# SparkFun_RTK_Facet_-_Main.net
KiCad netlist of a schematic drawn in EAGLE
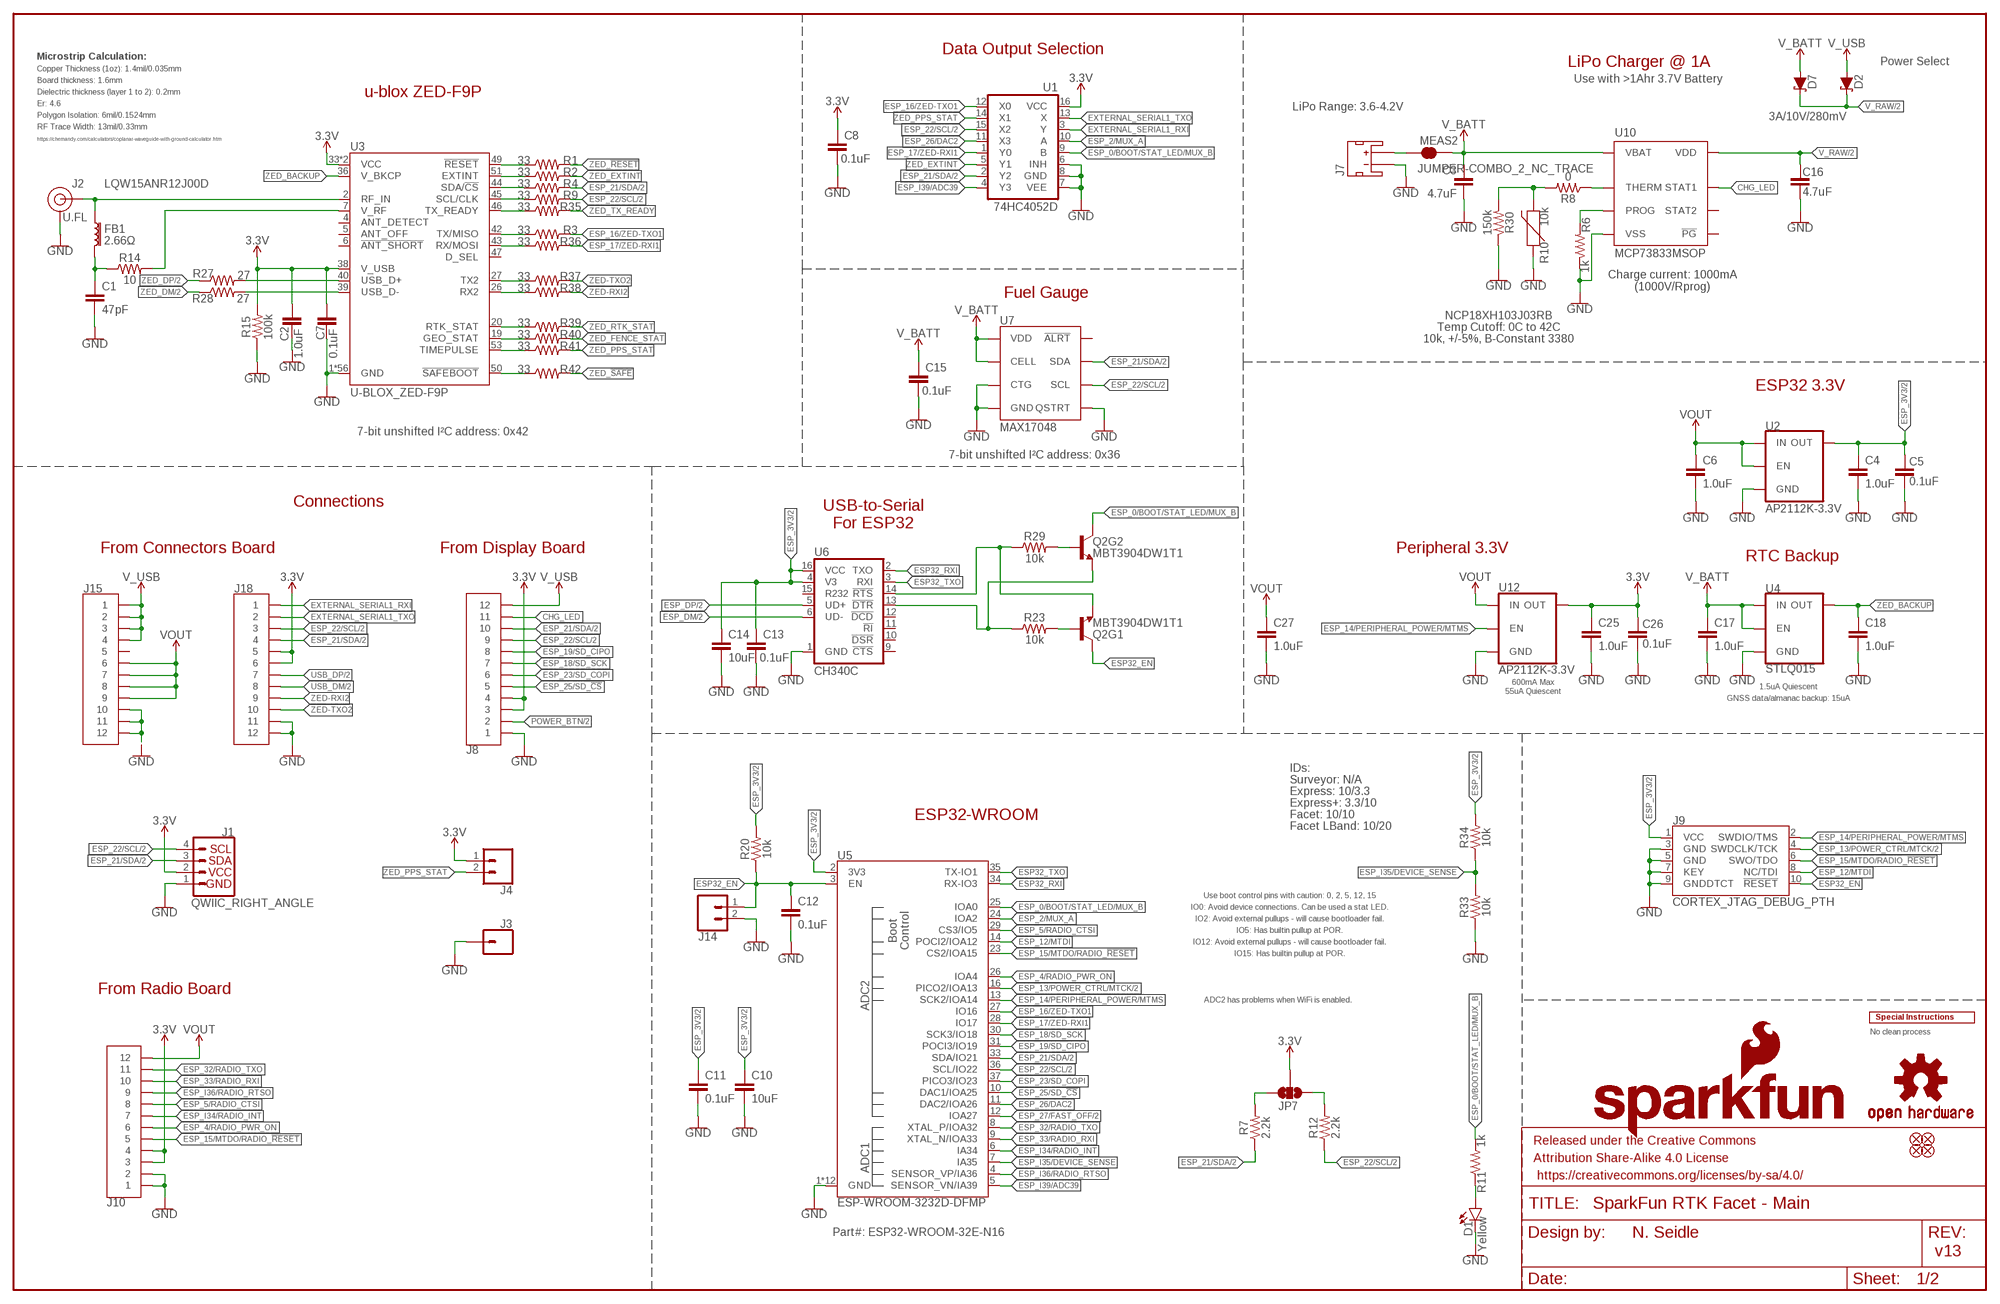
[diagram p0: schematic, sheet 1]
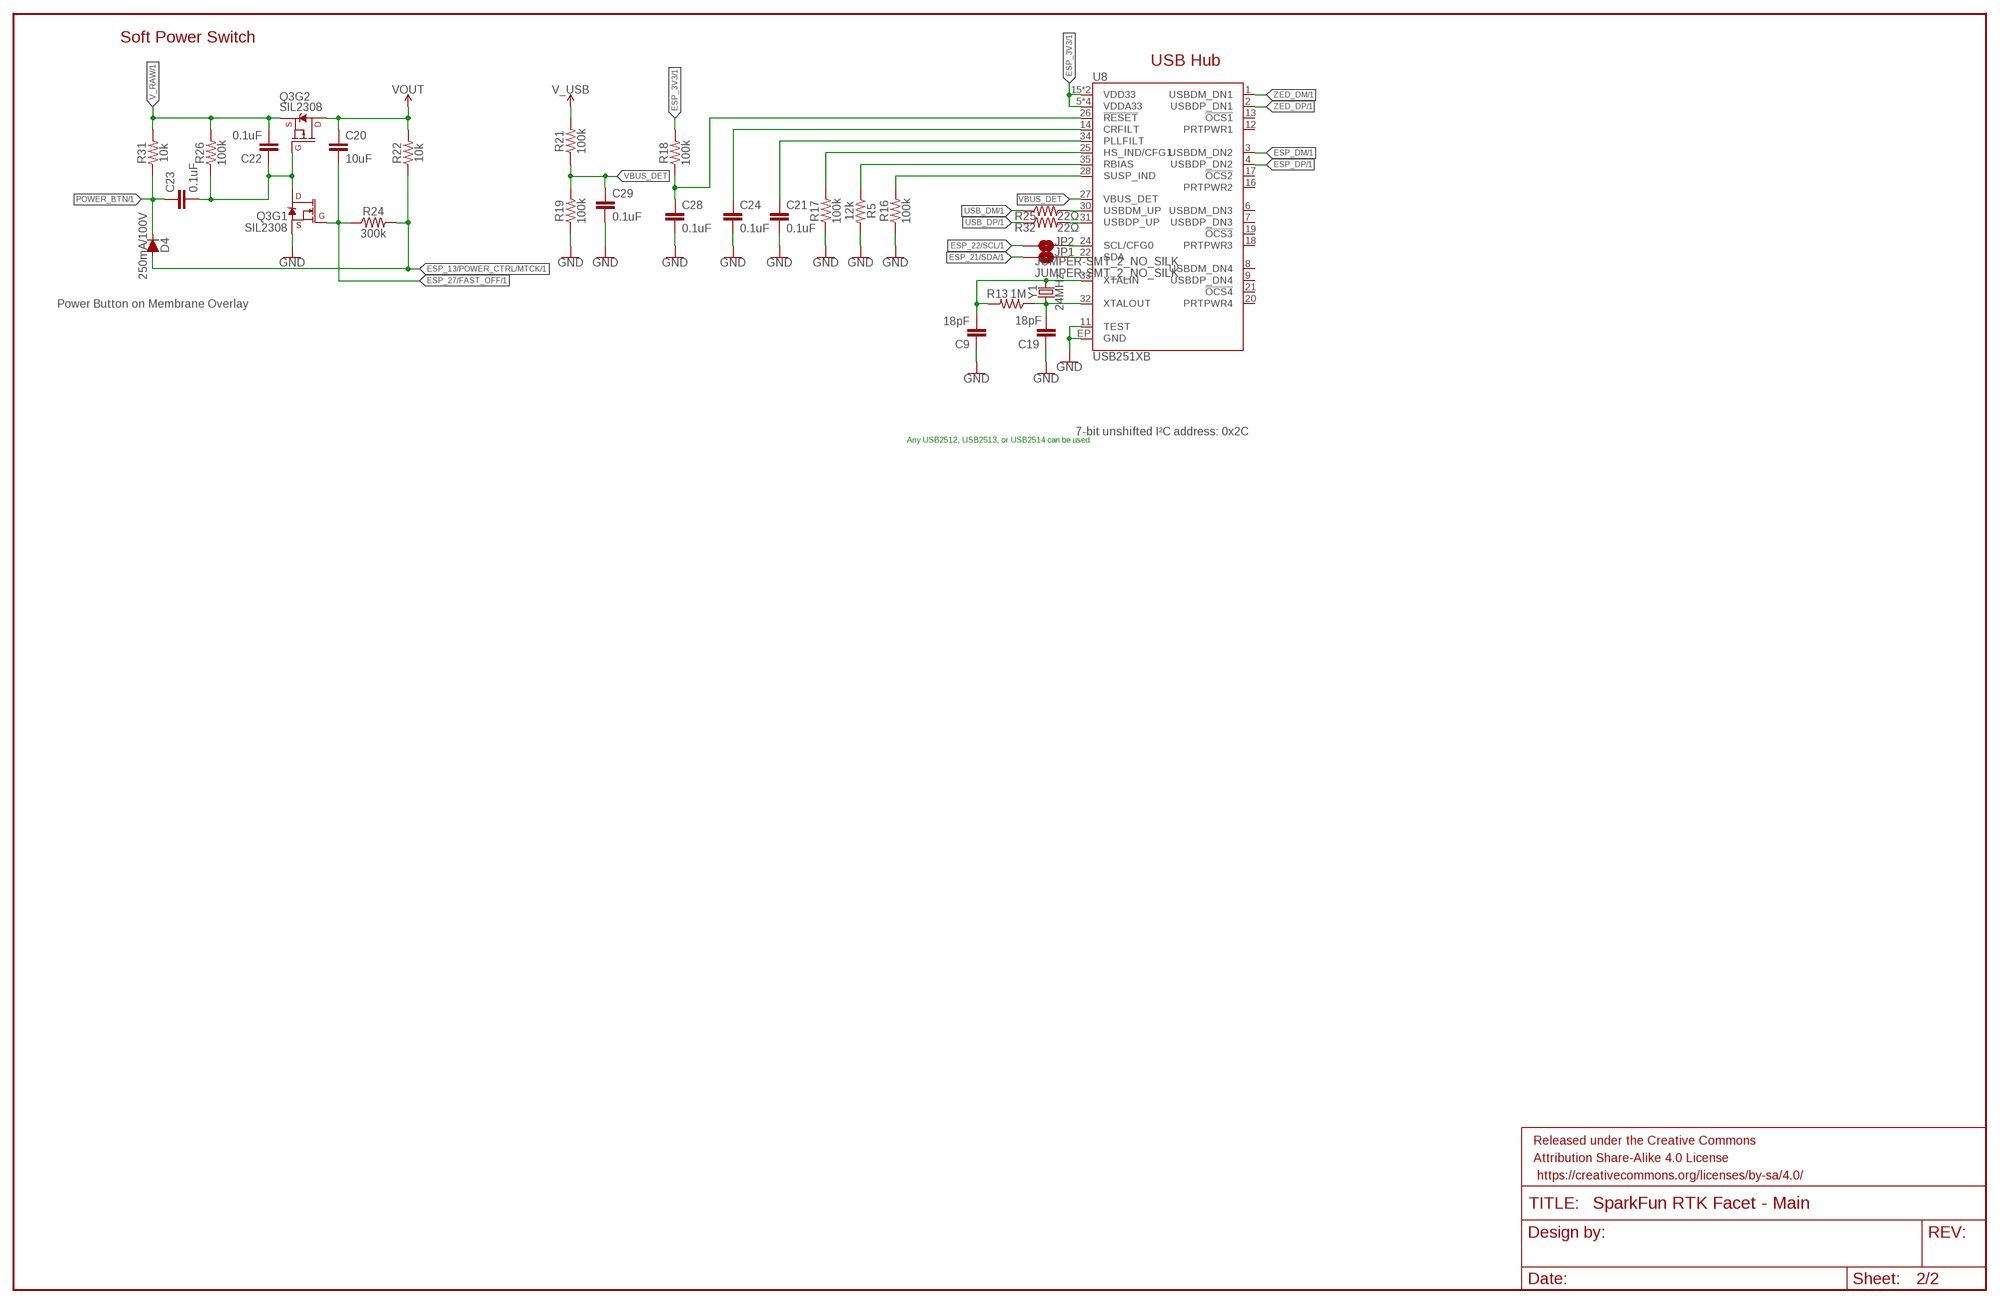
[diagram p1: schematic, sheet 2]

(export (version "E")
  (design (tool "Eeschema 10.0.6"))
  (components
    (comp (ref "C1")
      (value "47pF")
      (footprint "eagle-import:0402")
      (libsource (lib "eagle-import") (part "47PF-0402-25V-5%-X7R"))
    )
    (comp (ref "C2")
      (value "1.0uF")
      (footprint "eagle-import:0603")
      (libsource (lib "eagle-import") (part "1.0UF-0603-16V-10%-X7R"))
    )
    (comp (ref "C3")
      (value "4.7uF")
      (footprint "eagle-import:0603")
      (libsource (lib "eagle-import") (part "4.7UF-0603-35V-(20%)"))
    )
    (comp (ref "C4")
      (value "1.0uF")
      (footprint "eagle-import:0603")
      (libsource (lib "eagle-import") (part "1.0UF-0603-16V-10%-X7R"))
    )
    (comp (ref "C5")
      (value "0.1uF")
      (footprint "eagle-import:0603")
      (libsource (lib "eagle-import") (part "0.1UF-0603-25V-5%"))
    )
    (comp (ref "C6")
      (value "1.0uF")
      (footprint "eagle-import:0603")
      (libsource (lib "eagle-import") (part "1.0UF-0603-16V-10%-X7R"))
    )
    (comp (ref "C7")
      (value "0.1uF")
      (footprint "eagle-import:0603")
      (libsource (lib "eagle-import") (part "0.1UF-0603-25V-5%"))
    )
    (comp (ref "C8")
      (value "0.1uF")
      (footprint "eagle-import:0603")
      (libsource (lib "eagle-import") (part "0.1UF-0603-25V-(+80/-20%)"))
    )
    (comp (ref "C10")
      (value "10uF")
      (footprint "eagle-import:0603")
      (libsource (lib "eagle-import") (part "10UF-0603-6.3V-20%"))
    )
    (comp (ref "C11")
      (value "0.1uF")
      (footprint "eagle-import:0603")
      (libsource (lib "eagle-import") (part "0.1UF-0603-25V-(+80/-20%)"))
    )
    (comp (ref "C12")
      (value "0.1uF")
      (footprint "eagle-import:0603")
      (libsource (lib "eagle-import") (part "0.1UF-0603-25V-(+80/-20%)"))
    )
    (comp (ref "C13")
      (value "0.1uF")
      (footprint "eagle-import:0603")
      (libsource (lib "eagle-import") (part "0.1UF-0603-25V-(+80/-20%)"))
    )
    (comp (ref "C14")
      (value "10uF")
      (footprint "eagle-import:0603")
      (libsource (lib "eagle-import") (part "10UF-0603-6.3V-20%"))
    )
    (comp (ref "C15")
      (value "0.1uF")
      (footprint "eagle-import:0603")
      (libsource (lib "eagle-import") (part "0.1UF-0603-25V-(+80/-20%)"))
    )
    (comp (ref "C16")
      (value "4.7uF")
      (footprint "eagle-import:0603")
      (libsource (lib "eagle-import") (part "4.7UF-0603-35V-(20%)"))
    )
    (comp (ref "C17")
      (value "1.0uF")
      (footprint "eagle-import:0603")
      (libsource (lib "eagle-import") (part "1.0UF-0603-16V-10%-X7R"))
    )
    (comp (ref "C18")
      (value "1.0uF")
      (footprint "eagle-import:0603")
      (libsource (lib "eagle-import") (part "1.0UF-0603-16V-10%-X7R"))
    )
    (comp (ref "C25")
      (value "1.0uF")
      (footprint "eagle-import:0603")
      (libsource (lib "eagle-import") (part "1.0UF-0603-16V-10%-X7R"))
    )
    (comp (ref "C26")
      (value "0.1uF")
      (footprint "eagle-import:0603")
      (libsource (lib "eagle-import") (part "0.1UF-0603-25V-5%"))
    )
    (comp (ref "C27")
      (value "1.0uF")
      (footprint "eagle-import:0603")
      (libsource (lib "eagle-import") (part "1.0UF-0603-16V-10%-X7R"))
    )
    (comp (ref "D1")
      (value "Yellow")
      (footprint "eagle-import:LED-0603")
      (libsource (lib "eagle-import") (part "LED-YELLOW0603"))
    )
    (comp (ref "D2")
      (value "3A/10V/280mV")
      (footprint "eagle-import:SOD-323")
      (libsource (lib "eagle-import") (part "DIODE-SCHOTTKY-BAT60A"))
    )
    (comp (ref "D7")
      (value "3A/10V/280mV")
      (footprint "eagle-import:SOD-323")
      (libsource (lib "eagle-import") (part "DIODE-SCHOTTKY-BAT60A"))
    )
    (comp (ref "FB1")
      (value "2.66Ω")
      (footprint "eagle-import:0402-TIGHT")
      (libsource (lib "eagle-import") (part "FERRITE_BEAD-0402-2.66Ω-1GHZ"))
    )
    (comp (ref "FRAME2")
      (value "FRAME-LEDGER")
      (footprint "eagle-import:CREATIVE_COMMONS")
      (libsource (lib "eagle-import") (part "FRAME-LEDGER"))
    )
    (comp (ref "J1")
      (value "QWIIC_RIGHT_ANGLE")
      (footprint "eagle-import:JST04_1MM_RA")
      (libsource (lib "eagle-import") (part "QWIIC_CONNECTORJS-1MM"))
    )
    (comp (ref "J2")
      (value "U.FL")
      (footprint "eagle-import:U.FL")
      (libsource (lib "eagle-import") (part "U.FL2PIN"))
    )
    (comp (ref "J3")
      (value "CONN_01PTH_NO_SILK_YES_STOP")
      (footprint "eagle-import:1X01_NO_SILK")
      (libsource (lib "eagle-import") (part "CONN_01PTH_NO_SILK_YES_STOP"))
    )
    (comp (ref "J4")
      (value "CONN_021X02_NO_SILK")
      (footprint "eagle-import:1X02_NO_SILK")
      (libsource (lib "eagle-import") (part "CONN_021X02_NO_SILK"))
    )
    (comp (ref "J7")
      (value "JST_2MM_MALE")
      (footprint "eagle-import:JST-2-SMD")
      (libsource (lib "eagle-import") (part "JST_2MM_MALE"))
    )
    (comp (ref "J8")
      (value "FPC_12_0.5MM_BACKFLIP")
      (footprint "eagle-import:FPC_12_DOUBLESIDED_BACKFLIP")
      (libsource (lib "eagle-import") (part "FPC_12_0.5MM_BACKFLIP"))
    )
    (comp (ref "J9")
      (value "CORTEX_JTAG_DEBUG_PTH")
      (footprint "eagle-import:2X5-PTH-1.27MM")
      (libsource (lib "eagle-import") (part "CORTEX_JTAG_DEBUG_PTH"))
    )
    (comp (ref "J10")
      (value "FPC_12_0.5MM_BACKFLIP")
      (footprint "eagle-import:FPC_12_DOUBLESIDED_BACKFLIP")
      (libsource (lib "eagle-import") (part "FPC_12_0.5MM_BACKFLIP"))
    )
    (comp (ref "J14")
      (value "CONN_021X02_NO_SILK")
      (footprint "eagle-import:1X02_NO_SILK")
      (libsource (lib "eagle-import") (part "CONN_021X02_NO_SILK"))
    )
    (comp (ref "J15")
      (value "FPC_12_0.5MM_BACKFLIP")
      (footprint "eagle-import:FPC_12_DOUBLESIDED_BACKFLIP")
      (libsource (lib "eagle-import") (part "FPC_12_0.5MM_BACKFLIP"))
    )
    (comp (ref "J18")
      (value "FPC_12_0.5MM_BACKFLIP")
      (footprint "eagle-import:FPC_12_DOUBLESIDED_BACKFLIP")
      (libsource (lib "eagle-import") (part "FPC_12_0.5MM_BACKFLIP"))
    )
    (comp (ref "JP7")
      (value "JUMPER-SMT_3_NO_SILK")
      (footprint "eagle-import:SMT-JUMPER_3_NO_SILK")
      (libsource (lib "eagle-import") (part "JUMPER-SMT_3_NO_SILK"))
    )
    (comp (ref "JP21")
      (value "FIDUCIALUFIDUCIAL")
      (footprint "eagle-import:FIDUCIAL-MICRO")
      (libsource (lib "eagle-import") (part "FIDUCIALUFIDUCIAL"))
    )
    (comp (ref "JP61")
      (value "FIDUCIALUFIDUCIAL")
      (footprint "eagle-import:FIDUCIAL-MICRO")
      (libsource (lib "eagle-import") (part "FIDUCIALUFIDUCIAL"))
    )
    (comp (ref "JP71")
      (value "FIDUCIALUFIDUCIAL")
      (footprint "eagle-import:FIDUCIAL-MICRO")
      (libsource (lib "eagle-import") (part "FIDUCIALUFIDUCIAL"))
    )
    (comp (ref "JP81")
      (value "FIDUCIALUFIDUCIAL")
      (footprint "eagle-import:FIDUCIAL-MICRO")
      (libsource (lib "eagle-import") (part "FIDUCIALUFIDUCIAL"))
    )
    (comp (ref "LOGO1")
      (value "OSHW-LOGOMINI")
      (footprint "eagle-import:OSHW-LOGO-MINI")
      (libsource (lib "eagle-import") (part "OSHW-LOGOMINI"))
    )
    (comp (ref "LOGO2")
      (value "SFE_LOGO_NAME_FLAME.1_INCH")
      (footprint "eagle-import:SFE_LOGO_NAME_FLAME_.1")
      (libsource (lib "eagle-import") (part "SFE_LOGO_NAME_FLAME.1_INCH"))
    )
    (comp (ref "MEAS2")
      (value "JUMPER-COMBO_2_NC_TRACE")
      (footprint "eagle-import:COMBO-JUMPER_2_NC_TRACE")
      (libsource (lib "eagle-import") (part "JUMPER-COMBO_2_NC_TRACE"))
    )
    (comp (ref "Q2")
      (value "MBT3904DW1T1")
      (footprint "eagle-import:SC70-6")
      (libsource (lib "eagle-import") (part "TRANS_NPN_DUAL-MBT3904DW1T1"))
    )
    (comp (ref "R1")
      (value "33")
      (footprint "eagle-import:0603")
      (libsource (lib "eagle-import") (part "33OHM-0603-1/10W-1%"))
    )
    (comp (ref "R2")
      (value "33")
      (footprint "eagle-import:0603")
      (libsource (lib "eagle-import") (part "33OHM-0603-1/10W-1%"))
    )
    (comp (ref "R3")
      (value "33")
      (footprint "eagle-import:0603")
      (libsource (lib "eagle-import") (part "33OHM-0603-1/10W-1%"))
    )
    (comp (ref "R4")
      (value "33")
      (footprint "eagle-import:0603")
      (libsource (lib "eagle-import") (part "33OHM-0603-1/10W-1%"))
    )
    (comp (ref "R6")
      (value "1k")
      (footprint "eagle-import:0603")
      (libsource (lib "eagle-import") (part "1KOHM-0603-1/10W-1%"))
    )
    (comp (ref "R7")
      (value "2.2k")
      (footprint "eagle-import:0603")
      (libsource (lib "eagle-import") (part "2.2KOHM-0603-1/10W-1%"))
    )
    (comp (ref "R8")
      (value "0")
      (footprint "eagle-import:0603")
      (libsource (lib "eagle-import") (part "0OHM-0603-1/10W"))
    )
    (comp (ref "R9")
      (value "33")
      (footprint "eagle-import:0603")
      (libsource (lib "eagle-import") (part "33OHM-0603-1/10W-1%"))
    )
    (comp (ref "R10")
      (value "10k")
      (footprint "eagle-import:0603")
      (libsource (lib "eagle-import") (part "NTC-THERMISTOR-0603"))
    )
    (comp (ref "R11")
      (value "1k")
      (footprint "eagle-import:0603")
      (libsource (lib "eagle-import") (part "1KOHM-0603-1/10W-1%"))
    )
    (comp (ref "R12")
      (value "2.2k")
      (footprint "eagle-import:0603")
      (libsource (lib "eagle-import") (part "2.2KOHM-0603-1/10W-1%"))
    )
    (comp (ref "R14")
      (value "10")
      (footprint "eagle-import:0603")
      (libsource (lib "eagle-import") (part "10OHM-0603-1/10W-1%"))
    )
    (comp (ref "R15")
      (value "100k")
      (footprint "eagle-import:0603")
      (libsource (lib "eagle-import") (part "100KOHM-0603-1/10W-1%"))
    )
    (comp (ref "R20")
      (value "10k")
      (footprint "eagle-import:0603")
      (libsource (lib "eagle-import") (part "10KOHM-0603-1/10W-1%"))
    )
    (comp (ref "R23")
      (value "10k")
      (footprint "eagle-import:0603")
      (libsource (lib "eagle-import") (part "10KOHM-0603-1/10W-1%"))
    )
    (comp (ref "R27")
      (value "27")
      (footprint "eagle-import:0603")
      (libsource (lib "eagle-import") (part "27OHM-0603-1/10W-1%"))
    )
    (comp (ref "R28")
      (value "27")
      (footprint "eagle-import:0603")
      (libsource (lib "eagle-import") (part "27OHM-0603-1/10W-1%"))
    )
    (comp (ref "R29")
      (value "10k")
      (footprint "eagle-import:0603")
      (libsource (lib "eagle-import") (part "10KOHM-0603-1/10W-1%"))
    )
    (comp (ref "R30")
      (value "150k")
      (footprint "eagle-import:0603")
      (libsource (lib "eagle-import") (part "150KOHM-0603-1/10W-1%"))
    )
    (comp (ref "R33")
      (value "10k")
      (footprint "eagle-import:0603")
      (libsource (lib "eagle-import") (part "10KOHM-0603-1/10W-1%"))
    )
    (comp (ref "R34")
      (value "10k")
      (footprint "eagle-import:0603")
      (libsource (lib "eagle-import") (part "10KOHM-0603-1/10W-1%"))
    )
    (comp (ref "R35")
      (value "33")
      (footprint "eagle-import:0603")
      (libsource (lib "eagle-import") (part "33OHM-0603-1/10W-1%"))
    )
    (comp (ref "R36")
      (value "33")
      (footprint "eagle-import:0603")
      (libsource (lib "eagle-import") (part "33OHM-0603-1/10W-1%"))
    )
    (comp (ref "R37")
      (value "33")
      (footprint "eagle-import:0603")
      (libsource (lib "eagle-import") (part "33OHM-0603-1/10W-1%"))
    )
    (comp (ref "R38")
      (value "33")
      (footprint "eagle-import:0603")
      (libsource (lib "eagle-import") (part "33OHM-0603-1/10W-1%"))
    )
    (comp (ref "R39")
      (value "33")
      (footprint "eagle-import:0603")
      (libsource (lib "eagle-import") (part "33OHM-0603-1/10W-1%"))
    )
    (comp (ref "R40")
      (value "33")
      (footprint "eagle-import:0603")
      (libsource (lib "eagle-import") (part "33OHM-0603-1/10W-1%"))
    )
    (comp (ref "R41")
      (value "33")
      (footprint "eagle-import:0603")
      (libsource (lib "eagle-import") (part "33OHM-0603-1/10W-1%"))
    )
    (comp (ref "R42")
      (value "33")
      (footprint "eagle-import:0603")
      (libsource (lib "eagle-import") (part "33OHM-0603-1/10W-1%"))
    )
    (comp (ref "U$2")
      (value "SPECIAL_INSTRUCTIONS-ORDERING")
      (footprint "eagle-import:ORDERING_INSTRUCTIONS")
      (libsource (lib "eagle-import") (part "SPECIAL_INSTRUCTIONS-ORDERING"))
    )
    (comp (ref "U1")
      (value "74HC4052D")
      (footprint "eagle-import:SO16")
      (libsource (lib "eagle-import") (part "744052DHC"))
    )
    (comp (ref "U2")
      (value "AP2112K-3.3V")
      (footprint "eagle-import:SOT23-5")
      (libsource (lib "eagle-import") (part "V_REG_AP2112K-3.3V"))
    )
    (comp (ref "U3")
      (value "U-BLOX_ZED-F9P")
      (footprint "eagle-import:ZED-F9P")
      (libsource (lib "eagle-import") (part "U-BLOX_ZED-F9P"))
    )
    (comp (ref "U4")
      (value "STLQ015")
      (footprint "eagle-import:SOT23-5")
      (libsource (lib "eagle-import") (part "STLQ015-3.3V"))
    )
    (comp (ref "U5")
      (value "ESP-WROOM-3232D-DFMP")
      (footprint "eagle-import:ESP-WROOM-32D-DFM_PASTE")
      (libsource (lib "eagle-import") (part "ESP-WROOM-3232D-DFMP"))
    )
    (comp (ref "U6")
      (value "CH340C")
      (footprint "eagle-import:SO016")
      (libsource (lib "eagle-import") (part "CH340C"))
    )
    (comp (ref "U7")
      (value "MAX17048")
      (footprint "eagle-import:DFN-8")
      (libsource (lib "eagle-import") (part "MAX17048DFN8"))
    )
    (comp (ref "U10")
      (value "MCP73833MSOP")
      (footprint "eagle-import:MSOP10")
      (libsource (lib "eagle-import") (part "MCP73833MSOP"))
    )
    (comp (ref "U12")
      (value "AP2112K-3.3V")
      (footprint "eagle-import:SOT23-5")
      (libsource (lib "eagle-import") (part "V_REG_AP2112K-3.3V"))
    )
    (comp (ref "C9")
      (value "18pF")
      (footprint "eagle-import:0603")
      (libsource (lib "eagle-import") (part "18PF-0603-50V-5%"))
    )
    (comp (ref "C19")
      (value "18pF")
      (footprint "eagle-import:0603")
      (libsource (lib "eagle-import") (part "18PF-0603-50V-5%"))
    )
    (comp (ref "C20")
      (value "10uF")
      (footprint "eagle-import:0603")
      (libsource (lib "eagle-import") (part "10UF-0603-6.3V-20%"))
    )
    (comp (ref "C21")
      (value "0.1uF")
      (footprint "eagle-import:0603")
      (libsource (lib "eagle-import") (part "0.1UF-0603-25V-5%"))
    )
    (comp (ref "C22")
      (value "0.1uF")
      (footprint "eagle-import:0603")
      (libsource (lib "eagle-import") (part "0.1UF-0603-25V-5%"))
    )
    (comp (ref "C23")
      (value "0.1uF")
      (footprint "eagle-import:0603")
      (libsource (lib "eagle-import") (part "0.1UF-0603-25V-5%"))
    )
    (comp (ref "C24")
      (value "0.1uF")
      (footprint "eagle-import:0603")
      (libsource (lib "eagle-import") (part "0.1UF-0603-25V-5%"))
    )
    (comp (ref "C28")
      (value "0.1uF")
      (footprint "eagle-import:0603")
      (libsource (lib "eagle-import") (part "0.1UF-0603-25V-5%"))
    )
    (comp (ref "C29")
      (value "0.1uF")
      (footprint "eagle-import:0603")
      (libsource (lib "eagle-import") (part "0.1UF-0603-25V-5%"))
    )
    (comp (ref "D4")
      (value "250mA/100V")
      (footprint "eagle-import:SOD-323")
      (libsource (lib "eagle-import") (part "DIODE-BAS16J"))
    )
    (comp (ref "FRAME1")
      (value "FRAME-LEDGER")
      (footprint "eagle-import:CREATIVE_COMMONS")
      (libsource (lib "eagle-import") (part "FRAME-LEDGER"))
    )
    (comp (ref "JP1")
      (value "JUMPER-SMT_2_NO_SILK")
      (footprint "eagle-import:SMT-JUMPER_2_NO_SILK")
      (libsource (lib "eagle-import") (part "JUMPER-SMT_2_NO_SILK"))
    )
    (comp (ref "JP2")
      (value "JUMPER-SMT_2_NO_SILK")
      (footprint "eagle-import:SMT-JUMPER_2_NO_SILK")
      (libsource (lib "eagle-import") (part "JUMPER-SMT_2_NO_SILK"))
    )
    (comp (ref "Q3")
      (value "SIL2308")
      (footprint "eagle-import:SOT26")
      (libsource (lib "eagle-import") (part "MOSFET_COMPLIMENTARY_PAIR-SIL2308"))
    )
    (comp (ref "R5")
      (value "12k")
      (footprint "eagle-import:0603")
      (libsource (lib "eagle-import") (part "12KOHM-0603-1/10W-1%"))
    )
    (comp (ref "R13")
      (value "1M")
      (footprint "eagle-import:0603")
      (libsource (lib "eagle-import") (part "1MOHM-0603-1/4W-5%"))
    )
    (comp (ref "R16")
      (value "100k")
      (footprint "eagle-import:0603")
      (libsource (lib "eagle-import") (part "100KOHM-0603-1/10W-1%"))
    )
    (comp (ref "R17")
      (value "100k")
      (footprint "eagle-import:0603")
      (libsource (lib "eagle-import") (part "100KOHM-0603-1/10W-1%"))
    )
    (comp (ref "R18")
      (value "100k")
      (footprint "eagle-import:0603")
      (libsource (lib "eagle-import") (part "100KOHM-0603-1/10W-1%"))
    )
    (comp (ref "R19")
      (value "100k")
      (footprint "eagle-import:0603")
      (libsource (lib "eagle-import") (part "100KOHM-0603-1/10W-1%"))
    )
    (comp (ref "R21")
      (value "100k")
      (footprint "eagle-import:0603")
      (libsource (lib "eagle-import") (part "100KOHM-0603-1/10W-1%"))
    )
    (comp (ref "R22")
      (value "10k")
      (footprint "eagle-import:0603")
      (libsource (lib "eagle-import") (part "10KOHM-0603-1/10W-1%"))
    )
    (comp (ref "R24")
      (value "300k")
      (footprint "eagle-import:0603")
      (libsource (lib "eagle-import") (part "300KOHM-0603-1/10W-1%"))
    )
    (comp (ref "R25")
      (value "22Ω")
      (footprint "eagle-import:0603")
      (libsource (lib "eagle-import") (part "22OHM-0603-1/10W-1%"))
    )
    (comp (ref "R26")
      (value "100k")
      (footprint "eagle-import:0603")
      (libsource (lib "eagle-import") (part "100KOHM-0603-1/10W-1%"))
    )
    (comp (ref "R31")
      (value "10k")
      (footprint "eagle-import:0603")
      (libsource (lib "eagle-import") (part "10KOHM-0603-1/10W-1%"))
    )
    (comp (ref "R32")
      (value "22Ω")
      (footprint "eagle-import:0603")
      (libsource (lib "eagle-import") (part "22OHM-0603-1/10W-1%"))
    )
    (comp (ref "U8")
      (value "USB251XB")
      (footprint "eagle-import:QFN-36")
      (libsource (lib "eagle-import") (part "USB251XB"))
    )
    (comp (ref "Y1")
      (value "24MHz")
      (footprint "eagle-import:CRYSTAL-SMD-2.0X1.6MM")
      (libsource (lib "eagle-import") (part "CRYSTAL-24MHZ-SMD-2.0X1.6MM"))
    )
  )
  (nets
    (net (code "1") (name "3.3V") (class "Default")
      (node (ref "C2") (pin "1") (pinfunction "1_1") (pintype "passive"))
      (node (ref "C25") (pin "1") (pinfunction "1_1") (pintype "passive"))
      (node (ref "C26") (pin "2") (pinfunction "2_2") (pintype "passive"))
      (node (ref "C7") (pin "2") (pinfunction "2_2") (pintype "passive"))
      (node (ref "C8") (pin "1") (pinfunction "1_1") (pintype "passive"))
      (node (ref "J1") (pin "2") (pinfunction "2_2") (pintype "power_in"))
      (node (ref "J10") (pin "3") (pinfunction "3_3") (pintype "bidirectional"))
      (node (ref "J10") (pin "4") (pinfunction "4_4") (pintype "bidirectional"))
      (node (ref "J18") (pin "5") (pinfunction "5_5") (pintype "bidirectional"))
      (node (ref "J18") (pin "6") (pinfunction "6_6") (pintype "bidirectional"))
      (node (ref "J4") (pin "1") (pinfunction "1_1") (pintype "passive"))
      (node (ref "J8") (pin "3") (pinfunction "3_3") (pintype "bidirectional"))
      (node (ref "J8") (pin "4") (pinfunction "4_4") (pintype "bidirectional"))
      (node (ref "JP7") (pin "2") (pinfunction "2_2") (pintype "passive"))
      (node (ref "R15") (pin "2") (pinfunction "2_2") (pintype "passive"))
      (node (ref "U1") (pin "16") (pinfunction "VCC_16") (pintype "power_in"))
      (node (ref "U12") (pin "5") (pinfunction "OUT_5") (pintype "passive"))
      (node (ref "U3") (pin "33") (pinfunction "VCC_33") (pintype "bidirectional"))
      (node (ref "U3") (pin "34") (pinfunction "VCC_34") (pintype "bidirectional"))
      (node (ref "U3") (pin "38") (pinfunction "V_USB_38") (pintype "bidirectional"))
    )
    (net (code "2") (name "CHG_LED") (class "Default")
      (node (ref "J8") (pin "11") (pinfunction "11_11") (pintype "bidirectional"))
      (node (ref "U10") (pin "3") (pinfunction "STAT1_3") (pintype "bidirectional"))
    )
    (net (code "3") (name "ESP32_EN") (class "Default")
      (node (ref "C12") (pin "1") (pinfunction "1_1") (pintype "passive"))
      (node (ref "J14") (pin "1") (pinfunction "1_1") (pintype "passive"))
      (node (ref "J9") (pin "10") (pinfunction "~{RESET}_10") (pintype "bidirectional"))
      (node (ref "Q2") (pin "3") (pinfunction "C_3") (pintype "passive"))
      (node (ref "R20") (pin "1") (pinfunction "1_1") (pintype "passive"))
      (node (ref "U5") (pin "3") (pinfunction "EN_3") (pintype "bidirectional"))
    )
    (net (code "4") (name "ESP32_RXI") (class "Default")
      (node (ref "U5") (pin "34") (pinfunction "RX-IO3_34") (pintype "bidirectional"))
      (node (ref "U6") (pin "2") (pinfunction "TXO_2") (pintype "bidirectional"))
    )
    (net (code "5") (name "ESP32_TXO") (class "Default")
      (node (ref "U5") (pin "35") (pinfunction "TX-IO1_35") (pintype "bidirectional"))
      (node (ref "U6") (pin "3") (pinfunction "RXI_3") (pintype "bidirectional"))
    )
    (net (code "6") (name "ESP_0{slash}BOOT{slash}STAT_LED{slash}MUX_B") (class "Default")
      (node (ref "Q2") (pin "6") (pinfunction "C_6") (pintype "passive"))
      (node (ref "R11") (pin "2") (pinfunction "2_2") (pintype "passive"))
      (node (ref "U1") (pin "9") (pinfunction "B_9") (pintype "input"))
      (node (ref "U5") (pin "25") (pinfunction "IOA0_25") (pintype "bidirectional"))
    )
    (net (code "7") (name "ESP_2{slash}MUX_A") (class "Default")
      (node (ref "U1") (pin "10") (pinfunction "A_10") (pintype "input"))
      (node (ref "U5") (pin "24") (pinfunction "IOA2_24") (pintype "bidirectional"))
    )
    (net (code "8") (name "ESP_3V3") (class "Default")
      (node (ref "C10") (pin "1") (pinfunction "1_1") (pintype "passive"))
      (node (ref "C11") (pin "1") (pinfunction "1_1") (pintype "passive"))
      (node (ref "C13") (pin "1") (pinfunction "1_1") (pintype "passive"))
      (node (ref "C14") (pin "1") (pinfunction "1_1") (pintype "passive"))
      (node (ref "C4") (pin "1") (pinfunction "1_1") (pintype "passive"))
      (node (ref "C5") (pin "2") (pinfunction "2_2") (pintype "passive"))
      (node (ref "J9") (pin "1") (pinfunction "VCC_1") (pintype "bidirectional"))
      (node (ref "R18") (pin "2") (pinfunction "2_2") (pintype "passive"))
      (node (ref "R20") (pin "2") (pinfunction "2_2") (pintype "passive"))
      (node (ref "R34") (pin "2") (pinfunction "2_2") (pintype "passive"))
      (node (ref "U2") (pin "5") (pinfunction "OUT_5") (pintype "passive"))
      (node (ref "U5") (pin "2") (pinfunction "3V3_2") (pintype "bidirectional"))
      (node (ref "U6") (pin "16") (pinfunction "VCC_16") (pintype "bidirectional"))
      (node (ref "U6") (pin "4") (pinfunction "V3_4") (pintype "bidirectional"))
      (node (ref "U8") (pin "10") (pinfunction "VDDA33_10") (pintype "bidirectional"))
      (node (ref "U8") (pin "15") (pinfunction "VDD33_15") (pintype "bidirectional"))
      (node (ref "U8") (pin "23") (pinfunction "VDD33_23") (pintype "bidirectional"))
      (node (ref "U8") (pin "29") (pinfunction "VDDA33_29") (pintype "bidirectional"))
      (node (ref "U8") (pin "36") (pinfunction "VDDA33_36") (pintype "bidirectional"))
      (node (ref "U8") (pin "5") (pinfunction "VDDA33_5") (pintype "bidirectional"))
    )
    (net (code "9") (name "ESP_4{slash}RADIO_PWR_ON") (class "Default")
      (node (ref "J10") (pin "6") (pinfunction "6_6") (pintype "bidirectional"))
      (node (ref "U5") (pin "26") (pinfunction "IOA4_26") (pintype "bidirectional"))
    )
    (net (code "10") (name "ESP_5{slash}RADIO_CTSI") (class "Default")
      (node (ref "J10") (pin "8") (pinfunction "8_8") (pintype "bidirectional"))
      (node (ref "U5") (pin "29") (pinfunction "CS3/IO5_29") (pintype "bidirectional"))
    )
    (net (code "11") (name "ESP_12{slash}MTDI") (class "Default")
      (node (ref "J9") (pin "8") (pinfunction "NC/TDI_8") (pintype "bidirectional"))
      (node (ref "U5") (pin "14") (pinfunction "POCI2/IOA12_14") (pintype "bidirectional"))
    )
    (net (code "12") (name "ESP_13{slash}POWER_CTRL{slash}MTCK") (class "Default")
      (node (ref "D4") (pin "A") (pinfunction "A_A") (pintype "passive"))
      (node (ref "J9") (pin "4") (pinfunction "SWDCLK/TCK_4") (pintype "bidirectional"))
      (node (ref "R22") (pin "1") (pinfunction "1_1") (pintype "passive"))
      (node (ref "R24") (pin "2") (pinfunction "2_2") (pintype "passive"))
      (node (ref "U5") (pin "16") (pinfunction "PICO2/IOA13_16") (pintype "bidirectional"))
    )
    (net (code "13") (name "ESP_14{slash}PERIPHERAL_POWER{slash}MTMS") (class "Default")
      (node (ref "J9") (pin "2") (pinfunction "SWDIO/TMS_2") (pintype "bidirectional"))
      (node (ref "U12") (pin "3") (pinfunction "EN_3") (pintype "input"))
      (node (ref "U5") (pin "13") (pinfunction "SCK2/IOA14_13") (pintype "bidirectional"))
    )
    (net (code "14") (name "ESP_15{slash}MTDO{slash}RADIO_~{RESET}") (class "Default")
      (node (ref "J10") (pin "5") (pinfunction "5_5") (pintype "bidirectional"))
      (node (ref "J9") (pin "6") (pinfunction "SWO/TDO_6") (pintype "bidirectional"))
      (node (ref "U5") (pin "23") (pinfunction "CS2/IOA15_23") (pintype "bidirectional"))
    )
    (net (code "15") (name "ESP_16{slash}ZED-TXO1") (class "Default")
      (node (ref "R3") (pin "2") (pinfunction "2_2") (pintype "passive"))
      (node (ref "U1") (pin "12") (pinfunction "X0_12") (pintype "bidirectional"))
      (node (ref "U5") (pin "27") (pinfunction "IO16_27") (pintype "bidirectional"))
    )
    (net (code "16") (name "ESP_17{slash}ZED-RXI1") (class "Default")
      (node (ref "R36") (pin "2") (pinfunction "2_2") (pintype "passive"))
      (node (ref "U1") (pin "1") (pinfunction "Y0_1") (pintype "bidirectional"))
      (node (ref "U5") (pin "28") (pinfunction "IO17_28") (pintype "bidirectional"))
    )
    (net (code "17") (name "ESP_18{slash}SD_SCK") (class "Default")
      (node (ref "J8") (pin "7") (pinfunction "7_7") (pintype "bidirectional"))
      (node (ref "U5") (pin "30") (pinfunction "SCK3/IO18_30") (pintype "bidirectional"))
    )
    (net (code "18") (name "ESP_19{slash}SD_CIPO") (class "Default")
      (node (ref "J8") (pin "8") (pinfunction "8_8") (pintype "bidirectional"))
      (node (ref "U5") (pin "31") (pinfunction "POCI3/IO19_31") (pintype "bidirectional"))
    )
    (net (code "19") (name "ESP_21{slash}SDA") (class "Default")
      (node (ref "J1") (pin "3") (pinfunction "3_3") (pintype "passive"))
      (node (ref "J18") (pin "4") (pinfunction "4_4") (pintype "bidirectional"))
      (node (ref "J8") (pin "10") (pinfunction "10_10") (pintype "bidirectional"))
      (node (ref "JP1") (pin "1") (pinfunction "1_1") (pintype "passive"))
      (node (ref "R4") (pin "2") (pinfunction "2_2") (pintype "passive"))
      (node (ref "R7") (pin "1") (pinfunction "1_1") (pintype "passive"))
      (node (ref "U1") (pin "2") (pinfunction "Y2_2") (pintype "bidirectional"))
      (node (ref "U5") (pin "33") (pinfunction "SDA/IO21_33") (pintype "bidirectional"))
      (node (ref "U7") (pin "8") (pinfunction "SDA_8") (pintype "input"))
    )
    (net (code "20") (name "ESP_22{slash}SCL") (class "Default")
      (node (ref "J1") (pin "4") (pinfunction "4_4") (pintype "passive"))
      (node (ref "J18") (pin "3") (pinfunction "3_3") (pintype "bidirectional"))
      (node (ref "J8") (pin "9") (pinfunction "9_9") (pintype "bidirectional"))
      (node (ref "JP2") (pin "1") (pinfunction "1_1") (pintype "passive"))
      (node (ref "R12") (pin "1") (pinfunction "1_1") (pintype "passive"))
      (node (ref "R9") (pin "2") (pinfunction "2_2") (pintype "passive"))
      (node (ref "U1") (pin "15") (pinfunction "X2_15") (pintype "bidirectional"))
      (node (ref "U5") (pin "36") (pinfunction "SCL/IO22_36") (pintype "bidirectional"))
      (node (ref "U7") (pin "7") (pinfunction "SCL_7") (pintype "output"))
    )
    (net (code "21") (name "ESP_23{slash}SD_COPI") (class "Default")
      (node (ref "J8") (pin "6") (pinfunction "6_6") (pintype "bidirectional"))
      (node (ref "U5") (pin "37") (pinfunction "PICO3/IO23_37") (pintype "bidirectional"))
    )
    (net (code "22") (name "ESP_25{slash}SD_~{CS}") (class "Default")
      (node (ref "J8") (pin "5") (pinfunction "5_5") (pintype "bidirectional"))
      (node (ref "U5") (pin "10") (pinfunction "DAC1/IOA25_10") (pintype "bidirectional"))
    )
    (net (code "23") (name "ESP_26{slash}DAC2") (class "Default")
      (node (ref "U1") (pin "11") (pinfunction "X3_11") (pintype "bidirectional"))
      (node (ref "U5") (pin "11") (pinfunction "DAC2/IOA26_11") (pintype "bidirectional"))
    )
    (net (code "24") (name "ESP_27{slash}FAST_OFF") (class "Default")
      (node (ref "C20") (pin "2") (pinfunction "2_2") (pintype "passive"))
      (node (ref "Q3") (pin "G1") (pinfunction "G_G1") (pintype "bidirectional"))
      (node (ref "R24") (pin "1") (pinfunction "1_1") (pintype "passive"))
      (node (ref "U5") (pin "12") (pinfunction "IOA27_12") (pintype "bidirectional"))
    )
    (net (code "25") (name "ESP_32{slash}RADIO_TXO") (class "Default")
      (node (ref "J10") (pin "11") (pinfunction "11_11") (pintype "bidirectional"))
      (node (ref "U5") (pin "8") (pinfunction "XTAL_P/IOA32_8") (pintype "bidirectional"))
    )
    (net (code "26") (name "ESP_33{slash}RADIO_RXI") (class "Default")
      (node (ref "J10") (pin "10") (pinfunction "10_10") (pintype "bidirectional"))
      (node (ref "U5") (pin "9") (pinfunction "XTAL_N/IOA33_9") (pintype "bidirectional"))
    )
    (net (code "27") (name "ESP_DM") (class "Default")
      (node (ref "U6") (pin "6") (pinfunction "UD-_6") (pintype "bidirectional"))
      (node (ref "U8") (pin "3") (pinfunction "USBDM_DN2_3") (pintype "bidirectional"))
    )
    (net (code "28") (name "ESP_DP") (class "Default")
      (node (ref "U6") (pin "5") (pinfunction "UD+_5") (pintype "bidirectional"))
      (node (ref "U8") (pin "4") (pinfunction "USBDP_DN2_4") (pintype "bidirectional"))
    )
    (net (code "29") (name "ESP_I34{slash}RADIO_INT") (class "Default")
      (node (ref "J10") (pin "7") (pinfunction "7_7") (pintype "bidirectional"))
      (node (ref "U5") (pin "6") (pinfunction "IA34_6") (pintype "bidirectional"))
    )
    (net (code "30") (name "ESP_I35{slash}DEVICE_SENSE") (class "Default")
      (node (ref "R33") (pin "2") (pinfunction "2_2") (pintype "passive"))
      (node (ref "R34") (pin "1") (pinfunction "1_1") (pintype "passive"))
      (node (ref "U5") (pin "7") (pinfunction "IA35_7") (pintype "bidirectional"))
    )
    (net (code "31") (name "ESP_I36{slash}RADIO_RTSO") (class "Default")
      (node (ref "J10") (pin "9") (pinfunction "9_9") (pintype "bidirectional"))
      (node (ref "U5") (pin "4") (pinfunction "SENSOR_VP/IA36_4") (pintype "bidirectional"))
    )
    (net (code "32") (name "ESP_I39{slash}ADC39") (class "Default")
      (node (ref "U1") (pin "4") (pinfunction "Y3_4") (pintype "bidirectional"))
      (node (ref "U5") (pin "5") (pinfunction "SENSOR_VN/IA39_5") (pintype "bidirectional"))
    )
    (net (code "33") (name "EXTERNAL_SERIAL1_RXI") (class "Default")
      (node (ref "J18") (pin "1") (pinfunction "1_1") (pintype "bidirectional"))
      (node (ref "U1") (pin "3") (pinfunction "Y_3") (pintype "bidirectional"))
    )
    (net (code "34") (name "EXTERNAL_SERIAL1_TXO") (class "Default")
      (node (ref "J18") (pin "2") (pinfunction "2_2") (pintype "bidirectional"))
      (node (ref "U1") (pin "13") (pinfunction "X_13") (pintype "bidirectional"))
    )
    (net (code "35") (name "GND") (class "Default")
      (node (ref "C1") (pin "2") (pinfunction "2_2") (pintype "passive"))
      (node (ref "C10") (pin "2") (pinfunction "2_2") (pintype "passive"))
      (node (ref "C11") (pin "2") (pinfunction "2_2") (pintype "passive"))
      (node (ref "C12") (pin "2") (pinfunction "2_2") (pintype "passive"))
      (node (ref "C13") (pin "2") (pinfunction "2_2") (pintype "passive"))
      (node (ref "C14") (pin "2") (pinfunction "2_2") (pintype "passive"))
      (node (ref "C15") (pin "2") (pinfunction "2_2") (pintype "passive"))
      (node (ref "C16") (pin "2") (pinfunction "2_2") (pintype "passive"))
      (node (ref "C17") (pin "2") (pinfunction "2_2") (pintype "passive"))
      (node (ref "C18") (pin "2") (pinfunction "2_2") (pintype "passive"))
      (node (ref "C19") (pin "1") (pinfunction "1_1") (pintype "passive"))
      (node (ref "C2") (pin "2") (pinfunction "2_2") (pintype "passive"))
      (node (ref "C21") (pin "2") (pinfunction "2_2") (pintype "passive"))
      (node (ref "C24") (pin "2") (pinfunction "2_2") (pintype "passive"))
      (node (ref "C25") (pin "2") (pinfunction "2_2") (pintype "passive"))
      (node (ref "C26") (pin "1") (pinfunction "1_1") (pintype "passive"))
      (node (ref "C27") (pin "2") (pinfunction "2_2") (pintype "passive"))
      (node (ref "C28") (pin "2") (pinfunction "2_2") (pintype "passive"))
      (node (ref "C29") (pin "2") (pinfunction "2_2") (pintype "passive"))
      (node (ref "C3") (pin "2") (pinfunction "2_2") (pintype "passive"))
      (node (ref "C4") (pin "2") (pinfunction "2_2") (pintype "passive"))
      (node (ref "C5") (pin "1") (pinfunction "1_1") (pintype "passive"))
      (node (ref "C6") (pin "2") (pinfunction "2_2") (pintype "passive"))
      (node (ref "C7") (pin "1") (pinfunction "1_1") (pintype "passive"))
      (node (ref "C8") (pin "2") (pinfunction "2_2") (pintype "passive"))
      (node (ref "C9") (pin "1") (pinfunction "1_1") (pintype "passive"))
      (node (ref "D1") (pin "C") (pinfunction "C_C") (pintype "passive"))
      (node (ref "J1") (pin "1") (pinfunction "1_1") (pintype "power_in"))
      (node (ref "J10") (pin "1") (pinfunction "1_1") (pintype "bidirectional"))
      (node (ref "J10") (pin "2") (pinfunction "2_2") (pintype "bidirectional"))
      (node (ref "J14") (pin "2") (pinfunction "2_2") (pintype "passive"))
      (node (ref "J15") (pin "10") (pinfunction "10_10") (pintype "bidirectional"))
      (node (ref "J15") (pin "11") (pinfunction "11_11") (pintype "bidirectional"))
      (node (ref "J15") (pin "12") (pinfunction "12_12") (pintype "bidirectional"))
      (node (ref "J18") (pin "11") (pinfunction "11_11") (pintype "bidirectional"))
      (node (ref "J18") (pin "12") (pinfunction "12_12") (pintype "bidirectional"))
      (node (ref "J2") (pin "1") (pinfunction "GND_1") (pintype "bidirectional"))
      (node (ref "J2") (pin "2") (pinfunction "GND_2") (pintype "bidirectional"))
      (node (ref "J3") (pin "1") (pinfunction "1_1") (pintype "passive"))
      (node (ref "J7") (pin "1") (pinfunction "-_1") (pintype "bidirectional"))
      (node (ref "J8") (pin "1") (pinfunction "1_1") (pintype "bidirectional"))
      (node (ref "J9") (pin "3") (pinfunction "GND_3") (pintype "bidirectional"))
      (node (ref "J9") (pin "5") (pinfunction "GND_5") (pintype "bidirectional"))
      (node (ref "J9") (pin "7") (pinfunction "KEY_7") (pintype "bidirectional"))
      (node (ref "J9") (pin "9") (pinfunction "GNDDTCT_9") (pintype "bidirectional"))
      (node (ref "Q3") (pin "S1") (pinfunction "S_S1") (pintype "bidirectional"))
      (node (ref "R10") (pin "1") (pinfunction "1_1") (pintype "bidirectional"))
      (node (ref "R15") (pin "1") (pinfunction "1_1") (pintype "passive"))
      (node (ref "R16") (pin "1") (pinfunction "1_1") (pintype "passive"))
      (node (ref "R17") (pin "1") (pinfunction "1_1") (pintype "passive"))
      (node (ref "R19") (pin "1") (pinfunction "1_1") (pintype "passive"))
      (node (ref "R30") (pin "1") (pinfunction "1_1") (pintype "passive"))
      (node (ref "R33") (pin "1") (pinfunction "1_1") (pintype "passive"))
      (node (ref "R5") (pin "2") (pinfunction "2_2") (pintype "passive"))
      (node (ref "R6") (pin "1") (pinfunction "1_1") (pintype "passive"))
      (node (ref "U1") (pin "6") (pinfunction "INH_6") (pintype "input"))
      (node (ref "U1") (pin "7") (pinfunction "VEE_7") (pintype "power_in"))
      (node (ref "U1") (pin "8") (pinfunction "GND_8") (pintype "power_in"))
      (node (ref "U10") (pin "5") (pinfunction "VSS_5") (pintype "bidirectional"))
      (node (ref "U12") (pin "2") (pinfunction "GND_2") (pintype "input"))
      (node (ref "U2") (pin "2") (pinfunction "GND_2") (pintype "input"))
      (node (ref "U3") (pin "1") (pinfunction "GND_1") (pintype "bidirectional"))
      (node (ref "U3") (pin "100") (pinfunction "GND_100") (pintype "bidirectional"))
      (node (ref "U3") (pin "101") (pinfunction "GND_101") (pintype "bidirectional"))
      (node (ref "U3") (pin "102") (pinfunction "GND_102") (pintype "bidirectional"))
      (node (ref "U3") (pin "12") (pinfunction "GND_12") (pintype "bidirectional"))
      (node (ref "U3") (pin "14") (pinfunction "GND_14") (pintype "bidirectional"))
      (node (ref "U3") (pin "3") (pinfunction "GND_3") (pintype "bidirectional"))
      (node (ref "U3") (pin "32") (pinfunction "GND_32") (pintype "bidirectional"))
      (node (ref "U3") (pin "37") (pinfunction "GND_37") (pintype "bidirectional"))
      (node (ref "U3") (pin "41") (pinfunction "GND_41") (pintype "bidirectional"))
      (node (ref "U3") (pin "48") (pinfunction "GND_48") (pintype "bidirectional"))
      (node (ref "U3") (pin "55") (pinfunction "GND_55") (pintype "bidirectional"))
      (node (ref "U3") (pin "56") (pinfunction "GND_56") (pintype "bidirectional"))
      (node (ref "U3") (pin "57") (pinfunction "GND_57") (pintype "bidirectional"))
      (node (ref "U3") (pin "58") (pinfunction "GND_58") (pintype "bidirectional"))
      (node (ref "U3") (pin "59") (pinfunction "GND_59") (pintype "bidirectional"))
      (node (ref "U3") (pin "60") (pinfunction "GND_60") (pintype "bidirectional"))
      (node (ref "U3") (pin "61") (pinfunction "GND_61") (pintype "bidirectional"))
      (node (ref "U3") (pin "62") (pinfunction "GND_62") (pintype "bidirectional"))
      (node (ref "U3") (pin "63") (pinfunction "GND_63") (pintype "bidirectional"))
      (node (ref "U3") (pin "64") (pinfunction "GND_64") (pintype "bidirectional"))
      (node (ref "U3") (pin "65") (pinfunction "GND_65") (pintype "bidirectional"))
      (node (ref "U3") (pin "66") (pinfunction "GND_66") (pintype "bidirectional"))
      (node (ref "U3") (pin "67") (pinfunction "GND_67") (pintype "bidirectional"))
      (node (ref "U3") (pin "68") (pinfunction "GND_68") (pintype "bidirectional"))
      (node (ref "U3") (pin "69") (pinfunction "GND_69") (pintype "bidirectional"))
      (node (ref "U3") (pin "70") (pinfunction "GND_70") (pintype "bidirectional"))
      (node (ref "U3") (pin "71") (pinfunction "GND_71") (pintype "bidirectional"))
      (node (ref "U3") (pin "72") (pinfunction "GND_72") (pintype "bidirectional"))
      (node (ref "U3") (pin "73") (pinfunction "GND_73") (pintype "bidirectional"))
      (node (ref "U3") (pin "74") (pinfunction "GND_74") (pintype "bidirectional"))
      (node (ref "U3") (pin "75") (pinfunction "GND_75") (pintype "bidirectional"))
      (node (ref "U3") (pin "76") (pinfunction "GND_76") (pintype "bidirectional"))
      (node (ref "U3") (pin "77") (pinfunction "GND_77") (pintype "bidirectional"))
      (node (ref "U3") (pin "78") (pinfunction "GND_78") (pintype "bidirectional"))
      (node (ref "U3") (pin "79") (pinfunction "GND_79") (pintype "bidirectional"))
      (node (ref "U3") (pin "80") (pinfunction "GND_80") (pintype "bidirectional"))
      (node (ref "U3") (pin "81") (pinfunction "GND_81") (pintype "bidirectional"))
      (node (ref "U3") (pin "82") (pinfunction "GND_82") (pintype "bidirectional"))
      (node (ref "U3") (pin "83") (pinfunction "GND_83") (pintype "bidirectional"))
      (node (ref "U3") (pin "84") (pinfunction "GND_84") (pintype "bidirectional"))
      (node (ref "U3") (pin "85") (pinfunction "GND_85") (pintype "bidirectional"))
      (node (ref "U3") (pin "86") (pinfunction "GND_86") (pintype "bidirectional"))
      (node (ref "U3") (pin "87") (pinfunction "GND_87") (pintype "bidirectional"))
      (node (ref "U3") (pin "88") (pinfunction "GND_88") (pintype "bidirectional"))
      (node (ref "U3") (pin "89") (pinfunction "GND_89") (pintype "bidirectional"))
      (node (ref "U3") (pin "90") (pinfunction "GND_90") (pintype "bidirectional"))
      (node (ref "U3") (pin "91") (pinfunction "GND_91") (pintype "bidirectional"))
      (node (ref "U3") (pin "92") (pinfunction "GND_92") (pintype "bidirectional"))
      (node (ref "U3") (pin "93") (pinfunction "GND_93") (pintype "bidirectional"))
      (node (ref "U3") (pin "94") (pinfunction "GND_94") (pintype "bidirectional"))
      (node (ref "U3") (pin "95") (pinfunction "GND_95") (pintype "bidirectional"))
      (node (ref "U3") (pin "96") (pinfunction "GND_96") (pintype "bidirectional"))
      (node (ref "U3") (pin "97") (pinfunction "GND_97") (pintype "bidirectional"))
      (node (ref "U3") (pin "98") (pinfunction "GND_98") (pintype "bidirectional"))
      (node (ref "U3") (pin "99") (pinfunction "GND_99") (pintype "bidirectional"))
      (node (ref "U4") (pin "2") (pinfunction "GND_2") (pintype "input"))
      (node (ref "U5") (pin "1") (pinfunction "GND_1") (pintype "bidirectional"))
      (node (ref "U5") (pin "15") (pinfunction "GND_15") (pintype "bidirectional"))
      (node (ref "U5") (pin "38") (pinfunction "GND_38") (pintype "bidirectional"))
      (node (ref "U5") (pin "GND") (pinfunction "GND_GND") (pintype "bidirectional"))
      (node (ref "U5") (pin "GNDT1") (pinfunction "GND_GNDT1") (pintype "bidirectional"))
      (node (ref "U5") (pin "GNDT2") (pinfunction "GND_GNDT2") (pintype "bidirectional"))
      (node (ref "U5") (pin "GNDT3") (pinfunction "GND_GNDT3") (pintype "bidirectional"))
      (node (ref "U5") (pin "GNDT4") (pinfunction "GND_GNDT4") (pintype "bidirectional"))
      (node (ref "U5") (pin "GNDT5") (pinfunction "GND_GNDT5") (pintype "bidirectional"))
      (node (ref "U5") (pin "GNDT6") (pinfunction "GND_GNDT6") (pintype "bidirectional"))
      (node (ref "U5") (pin "GNDT7") (pinfunction "GND_GNDT7") (pintype "bidirectional"))
      (node (ref "U5") (pin "GNDT8") (pinfunction "GND_GNDT8") (pintype "bidirectional"))
      (node (ref "U6") (pin "1") (pinfunction "GND_1") (pintype "bidirectional"))
      (node (ref "U7") (pin "1") (pinfunction "CTG_1") (pintype "input"))
      (node (ref "U7") (pin "4") (pinfunction "GND_4") (pintype "bidirectional"))
      (node (ref "U7") (pin "6") (pinfunction "QSTRT_6") (pintype "bidirectional"))
      (node (ref "U7") (pin "9") (pinfunction "GND_9") (pintype "bidirectional"))
      (node (ref "U8") (pin "11") (pinfunction "TEST_11") (pintype "bidirectional"))
      (node (ref "U8") (pin "EP") (pinfunction "GND_EP") (pintype "bidirectional"))
    )
    (net (code "36") (name "Net-(C1-Pad1)") (class "Default")
      (node (ref "C1") (pin "1") (pinfunction "1_1") (pintype "passive"))
      (node (ref "FB1") (pin "2") (pinfunction "2_2") (pintype "passive"))
      (node (ref "R14") (pin "1") (pinfunction "1_1") (pintype "passive"))
    )
    (net (code "37") (name "Net-(D1-PadA)") (class "Default")
      (node (ref "D1") (pin "A") (pinfunction "A_A") (pintype "passive"))
      (node (ref "R11") (pin "1") (pinfunction "1_1") (pintype "passive"))
    )
    (net (code "38") (name "Net-(J2-SIGNAL)") (class "Default")
      (node (ref "FB1") (pin "1") (pinfunction "1_1") (pintype "passive"))
      (node (ref "J2") (pin "FEED") (pinfunction "SIGNAL_FEED") (pintype "bidirectional"))
      (node (ref "U3") (pin "2") (pinfunction "RF_IN_2") (pintype "bidirectional"))
    )
    (net (code "39") (name "Net-(J7-+)") (class "Default")
      (node (ref "J7") (pin "2") (pinfunction "+_2") (pintype "bidirectional"))
      (node (ref "MEAS2") (pin "1") (pinfunction "1_1") (pintype "passive"))
      (node (ref "MEAS2") (pin "3") (pinfunction "1_3") (pintype "passive"))
    )
    (net (code "40") (name "Net-(JP7-Pad1)") (class "Default")
      (node (ref "JP7") (pin "1") (pinfunction "1_1") (pintype "passive"))
      (node (ref "R12") (pin "2") (pinfunction "2_2") (pintype "passive"))
    )
    (net (code "41") (name "Net-(JP7-Pad3)") (class "Default")
      (node (ref "JP7") (pin "3") (pinfunction "3_3") (pintype "passive"))
      (node (ref "R7") (pin "2") (pinfunction "2_2") (pintype "passive"))
    )
    (net (code "42") (name "Net-(Q2A-B)") (class "Default")
      (node (ref "Q2") (pin "5") (pinfunction "B_5") (pintype "passive"))
      (node (ref "R23") (pin "2") (pinfunction "2_2") (pintype "passive"))
    )
    (net (code "43") (name "Net-(Q2A-E)") (class "Default")
      (node (ref "Q2") (pin "4") (pinfunction "E_4") (pintype "passive"))
      (node (ref "R29") (pin "1") (pinfunction "1_1") (pintype "passive"))
      (node (ref "U6") (pin "14") (pinfunction "~{RTS}_14") (pintype "bidirectional"))
    )
    (net (code "44") (name "Net-(Q2B-B)") (class "Default")
      (node (ref "Q2") (pin "2") (pinfunction "B_2") (pintype "passive"))
      (node (ref "R29") (pin "2") (pinfunction "2_2") (pintype "passive"))
    )
    (net (code "45") (name "Net-(Q2B-E)") (class "Default")
      (node (ref "Q2") (pin "1") (pinfunction "E_1") (pintype "passive"))
      (node (ref "R23") (pin "1") (pinfunction "1_1") (pintype "passive"))
      (node (ref "U6") (pin "13") (pinfunction "~{DTR}_13") (pintype "bidirectional"))
    )
    (net (code "46") (name "Net-(Q3A-D)") (class "Default")
      (node (ref "C22") (pin "1") (pinfunction "1_1") (pintype "passive"))
      (node (ref "C23") (pin "2") (pinfunction "2_2") (pintype "passive"))
      (node (ref "Q3") (pin "D1") (pinfunction "D_D1") (pintype "bidirectional"))
      (node (ref "Q3") (pin "G2") (pinfunction "G_G2") (pintype "bidirectional"))
      (node (ref "R26") (pin "1") (pinfunction "1_1") (pintype "passive"))
    )
    (net (code "47") (name "Net-(R10-Pad2)") (class "Default")
      (node (ref "R10") (pin "2") (pinfunction "2_2") (pintype "bidirectional"))
      (node (ref "R30") (pin "2") (pinfunction "2_2") (pintype "passive"))
      (node (ref "R8") (pin "2") (pinfunction "2_2") (pintype "passive"))
    )
    (net (code "48") (name "Net-(U3-EXTINT)") (class "Default")
      (node (ref "R2") (pin "1") (pinfunction "1_1") (pintype "passive"))
      (node (ref "U3") (pin "51") (pinfunction "EXTINT_51") (pintype "bidirectional"))
    )
    (net (code "49") (name "Net-(U3-GEO_STAT)") (class "Default")
      (node (ref "R40") (pin "1") (pinfunction "1_1") (pintype "passive"))
      (node (ref "U3") (pin "19") (pinfunction "GEO_STAT_19") (pintype "bidirectional"))
    )
    (net (code "50") (name "Net-(U3-RTK_STAT)") (class "Default")
      (node (ref "R39") (pin "1") (pinfunction "1_1") (pintype "passive"))
      (node (ref "U3") (pin "20") (pinfunction "RTK_STAT_20") (pintype "bidirectional"))
    )
    (net (code "51") (name "Net-(U3-RX2)") (class "Default")
      (node (ref "R38") (pin "1") (pinfunction "1_1") (pintype "passive"))
      (node (ref "U3") (pin "26") (pinfunction "RX2_26") (pintype "bidirectional"))
    )
    (net (code "52") (name "Net-(U3-RX{slash}MOSI)") (class "Default")
      (node (ref "R36") (pin "1") (pinfunction "1_1") (pintype "passive"))
      (node (ref "U3") (pin "43") (pinfunction "RX/MOSI_43") (pintype "bidirectional"))
    )
    (net (code "53") (name "Net-(U3-SCL{slash}CLK)") (class "Default")
      (node (ref "R9") (pin "1") (pinfunction "1_1") (pintype "passive"))
      (node (ref "U3") (pin "45") (pinfunction "SCL/CLK_45") (pintype "bidirectional"))
    )
    (net (code "54") (name "Net-(U3-SDA{slash}~{CS})") (class "Default")
      (node (ref "R4") (pin "1") (pinfunction "1_1") (pintype "passive"))
      (node (ref "U3") (pin "44") (pinfunction "SDA/~{CS}_44") (pintype "bidirectional"))
    )
    (net (code "55") (name "Net-(U3-TIMEPULSE)") (class "Default")
      (node (ref "R41") (pin "1") (pinfunction "1_1") (pintype "passive"))
      (node (ref "U3") (pin "53") (pinfunction "TIMEPULSE_53") (pintype "bidirectional"))
    )
    (net (code "56") (name "Net-(U3-TX2)") (class "Default")
      (node (ref "R37") (pin "1") (pinfunction "1_1") (pintype "passive"))
      (node (ref "U3") (pin "27") (pinfunction "TX2_27") (pintype "bidirectional"))
    )
    (net (code "57") (name "Net-(U3-TX_READY)") (class "Default")
      (node (ref "R35") (pin "1") (pinfunction "1_1") (pintype "passive"))
      (node (ref "U3") (pin "46") (pinfunction "TX_READY_46") (pintype "bidirectional"))
    )
    (net (code "58") (name "Net-(U3-TX{slash}MISO)") (class "Default")
      (node (ref "R3") (pin "1") (pinfunction "1_1") (pintype "passive"))
      (node (ref "U3") (pin "42") (pinfunction "TX/MISO_42") (pintype "bidirectional"))
    )
    (net (code "59") (name "Net-(U3-USB_D+)") (class "Default")
      (node (ref "R27") (pin "2") (pinfunction "2_2") (pintype "passive"))
      (node (ref "U3") (pin "40") (pinfunction "USB_D+_40") (pintype "bidirectional"))
    )
    (net (code "60") (name "Net-(U3-USB_D-)") (class "Default")
      (node (ref "R28") (pin "2") (pinfunction "2_2") (pintype "passive"))
      (node (ref "U3") (pin "39") (pinfunction "USB_D-_39") (pintype "bidirectional"))
    )
    (net (code "61") (name "Net-(U3-V_RF)") (class "Default")
      (node (ref "R14") (pin "2") (pinfunction "2_2") (pintype "passive"))
      (node (ref "U3") (pin "7") (pinfunction "V_RF_7") (pintype "bidirectional"))
    )
    (net (code "62") (name "Net-(U3-~{RESET})") (class "Default")
      (node (ref "R1") (pin "1") (pinfunction "1_1") (pintype "passive"))
      (node (ref "U3") (pin "49") (pinfunction "~{RESET}_49") (pintype "bidirectional"))
    )
    (net (code "63") (name "Net-(U3-~{SAFEBOOT})") (class "Default")
      (node (ref "R42") (pin "1") (pinfunction "1_1") (pintype "passive"))
      (node (ref "U3") (pin "50") (pinfunction "~{SAFEBOOT}_50") (pintype "bidirectional"))
    )
    (net (code "64") (name "Net-(U8-CRFILT)") (class "Default")
      (node (ref "C24") (pin "1") (pinfunction "1_1") (pintype "passive"))
      (node (ref "U8") (pin "14") (pinfunction "CRFILT_14") (pintype "bidirectional"))
    )
    (net (code "65") (name "Net-(U8-HS_IND{slash}CFG1)") (class "Default")
      (node (ref "R17") (pin "2") (pinfunction "2_2") (pintype "passive"))
      (node (ref "U8") (pin "25") (pinfunction "HS_IND/CFG1_25") (pintype "bidirectional"))
    )
    (net (code "66") (name "Net-(U8-PLLFILT)") (class "Default")
      (node (ref "C21") (pin "1") (pinfunction "1_1") (pintype "passive"))
      (node (ref "U8") (pin "34") (pinfunction "PLLFILT_34") (pintype "bidirectional"))
    )
    (net (code "67") (name "Net-(U8-RBIAS)") (class "Default")
      (node (ref "R5") (pin "1") (pinfunction "1_1") (pintype "passive"))
      (node (ref "U8") (pin "35") (pinfunction "RBIAS_35") (pintype "bidirectional"))
    )
    (net (code "68") (name "Net-(U8-SCL{slash}CFG0)") (class "Default")
      (node (ref "JP2") (pin "2") (pinfunction "2_2") (pintype "passive"))
      (node (ref "U8") (pin "24") (pinfunction "SCL/CFG0_24") (pintype "bidirectional"))
    )
    (net (code "69") (name "Net-(U8-SDA)") (class "Default")
      (node (ref "JP1") (pin "2") (pinfunction "2_2") (pintype "passive"))
      (node (ref "U8") (pin "22") (pinfunction "SDA_22") (pintype "bidirectional"))
    )
    (net (code "70") (name "Net-(U8-SUSP_IND)") (class "Default")
      (node (ref "R16") (pin "2") (pinfunction "2_2") (pintype "passive"))
      (node (ref "U8") (pin "28") (pinfunction "SUSP_IND_28") (pintype "bidirectional"))
    )
    (net (code "71") (name "Net-(U8-USBDM_UP)") (class "Default")
      (node (ref "R25") (pin "2") (pinfunction "2_2") (pintype "passive"))
      (node (ref "U8") (pin "30") (pinfunction "USBDM_UP_30") (pintype "bidirectional"))
    )
    (net (code "72") (name "Net-(U8-USBDP_UP)") (class "Default")
      (node (ref "R32") (pin "2") (pinfunction "2_2") (pintype "passive"))
      (node (ref "U8") (pin "31") (pinfunction "USBDP_UP_31") (pintype "bidirectional"))
    )
    (net (code "73") (name "Net-(U8-XTALIN)") (class "Default")
      (node (ref "C9") (pin "2") (pinfunction "2_2") (pintype "passive"))
      (node (ref "R13") (pin "2") (pinfunction "2_2") (pintype "passive"))
      (node (ref "U8") (pin "33") (pinfunction "XTALIN_33") (pintype "bidirectional"))
      (node (ref "Y1") (pin "3") (pinfunction "2_3") (pintype "passive"))
    )
    (net (code "74") (name "Net-(U8-XTALOUT)") (class "Default")
      (node (ref "C19") (pin "2") (pinfunction "2_2") (pintype "passive"))
      (node (ref "R13") (pin "1") (pinfunction "1_1") (pintype "passive"))
      (node (ref "U8") (pin "32") (pinfunction "XTALOUT_32") (pintype "bidirectional"))
      (node (ref "Y1") (pin "1") (pinfunction "1_1") (pintype "passive"))
    )
    (net (code "75") (name "Net-(U8-~{RESET})") (class "Default")
      (node (ref "C28") (pin "1") (pinfunction "1_1") (pintype "passive"))
      (node (ref "R18") (pin "1") (pinfunction "1_1") (pintype "passive"))
      (node (ref "U8") (pin "26") (pinfunction "~{RESET}_26") (pintype "bidirectional"))
    )
    (net (code "76") (name "Net-(U10-PROG)") (class "Default")
      (node (ref "R6") (pin "2") (pinfunction "2_2") (pintype "passive"))
      (node (ref "U10") (pin "6") (pinfunction "PROG_6") (pintype "bidirectional"))
    )
    (net (code "77") (name "Net-(U10-THERM)") (class "Default")
      (node (ref "R8") (pin "1") (pinfunction "1_1") (pintype "passive"))
      (node (ref "U10") (pin "8") (pinfunction "THERM_8") (pintype "bidirectional"))
    )
    (net (code "78") (name "POWER_BTN") (class "Default")
      (node (ref "C23") (pin "1") (pinfunction "1_1") (pintype "passive"))
      (node (ref "D4") (pin "C") (pinfunction "C_C") (pintype "passive"))
      (node (ref "J8") (pin "2") (pinfunction "2_2") (pintype "bidirectional"))
      (node (ref "R31") (pin "1") (pinfunction "1_1") (pintype "passive"))
    )
    (net (code "79") (name "USB_DM") (class "Default")
      (node (ref "J18") (pin "8") (pinfunction "8_8") (pintype "bidirectional"))
      (node (ref "R25") (pin "1") (pinfunction "1_1") (pintype "passive"))
    )
    (net (code "80") (name "USB_DP") (class "Default")
      (node (ref "J18") (pin "7") (pinfunction "7_7") (pintype "bidirectional"))
      (node (ref "R32") (pin "1") (pinfunction "1_1") (pintype "passive"))
    )
    (net (code "81") (name "VBUS_DET") (class "Default")
      (node (ref "C29") (pin "1") (pinfunction "1_1") (pintype "passive"))
      (node (ref "R19") (pin "2") (pinfunction "2_2") (pintype "passive"))
      (node (ref "R21") (pin "1") (pinfunction "1_1") (pintype "passive"))
      (node (ref "U8") (pin "27") (pinfunction "VBUS_DET_27") (pintype "bidirectional"))
    )
    (net (code "82") (name "VOUT") (class "Default")
      (node (ref "C20") (pin "1") (pinfunction "1_1") (pintype "passive"))
      (node (ref "C27") (pin "1") (pinfunction "1_1") (pintype "passive"))
      (node (ref "C6") (pin "1") (pinfunction "1_1") (pintype "passive"))
      (node (ref "J10") (pin "12") (pinfunction "12_12") (pintype "bidirectional"))
      (node (ref "J15") (pin "6") (pinfunction "6_6") (pintype "bidirectional"))
      (node (ref "J15") (pin "7") (pinfunction "7_7") (pintype "bidirectional"))
      (node (ref "J15") (pin "8") (pinfunction "8_8") (pintype "bidirectional"))
      (node (ref "J15") (pin "9") (pinfunction "9_9") (pintype "bidirectional"))
      (node (ref "Q3") (pin "D2") (pinfunction "D_D2") (pintype "bidirectional"))
      (node (ref "R22") (pin "2") (pinfunction "2_2") (pintype "passive"))
      (node (ref "U12") (pin "1") (pinfunction "IN_1") (pintype "input"))
      (node (ref "U2") (pin "1") (pinfunction "IN_1") (pintype "input"))
      (node (ref "U2") (pin "3") (pinfunction "EN_3") (pintype "input"))
    )
    (net (code "83") (name "V_BATT") (class "Default")
      (node (ref "C15") (pin "1") (pinfunction "1_1") (pintype "passive"))
      (node (ref "C17") (pin "1") (pinfunction "1_1") (pintype "passive"))
      (node (ref "C3") (pin "1") (pinfunction "1_1") (pintype "passive"))
      (node (ref "D7") (pin "A") (pinfunction "A_A") (pintype "passive"))
      (node (ref "MEAS2") (pin "2") (pinfunction "2_2") (pintype "passive"))
      (node (ref "MEAS2") (pin "4") (pinfunction "2_4") (pintype "passive"))
      (node (ref "U10") (pin "10") (pinfunction "VBAT_10") (pintype "bidirectional"))
      (node (ref "U10") (pin "9") (pinfunction "VBAT_9") (pintype "bidirectional"))
      (node (ref "U4") (pin "1") (pinfunction "IN_1") (pintype "input"))
      (node (ref "U4") (pin "3") (pinfunction "EN_3") (pintype "input"))
      (node (ref "U7") (pin "2") (pinfunction "CELL_2") (pintype "input"))
      (node (ref "U7") (pin "3") (pinfunction "VDD_3") (pintype "bidirectional"))
    )
    (net (code "84") (name "V_RAW") (class "Default")
      (node (ref "C16") (pin "1") (pinfunction "1_1") (pintype "passive"))
      (node (ref "C22") (pin "2") (pinfunction "2_2") (pintype "passive"))
      (node (ref "D2") (pin "C") (pinfunction "C_C") (pintype "passive"))
      (node (ref "D7") (pin "C") (pinfunction "C_C") (pintype "passive"))
      (node (ref "Q3") (pin "S2") (pinfunction "S_S2") (pintype "bidirectional"))
      (node (ref "R26") (pin "2") (pinfunction "2_2") (pintype "passive"))
      (node (ref "R31") (pin "2") (pinfunction "2_2") (pintype "passive"))
      (node (ref "U10") (pin "1") (pinfunction "VDD_1") (pintype "bidirectional"))
      (node (ref "U10") (pin "2") (pinfunction "VDD_2") (pintype "bidirectional"))
    )
    (net (code "85") (name "V_USB") (class "Default")
      (node (ref "D2") (pin "A") (pinfunction "A_A") (pintype "passive"))
      (node (ref "J15") (pin "1") (pinfunction "1_1") (pintype "bidirectional"))
      (node (ref "J15") (pin "2") (pinfunction "2_2") (pintype "bidirectional"))
      (node (ref "J15") (pin "3") (pinfunction "3_3") (pintype "bidirectional"))
      (node (ref "J15") (pin "4") (pinfunction "4_4") (pintype "bidirectional"))
      (node (ref "J8") (pin "12") (pinfunction "12_12") (pintype "bidirectional"))
      (node (ref "R21") (pin "2") (pinfunction "2_2") (pintype "passive"))
    )
    (net (code "86") (name "ZED-RXI2") (class "Default")
      (node (ref "J18") (pin "9") (pinfunction "9_9") (pintype "bidirectional"))
      (node (ref "R38") (pin "2") (pinfunction "2_2") (pintype "passive"))
    )
    (net (code "87") (name "ZED-TXO2") (class "Default")
      (node (ref "J18") (pin "10") (pinfunction "10_10") (pintype "bidirectional"))
      (node (ref "R37") (pin "2") (pinfunction "2_2") (pintype "passive"))
    )
    (net (code "88") (name "ZED_BACKUP") (class "Default")
      (node (ref "C18") (pin "1") (pinfunction "1_1") (pintype "passive"))
      (node (ref "U3") (pin "36") (pinfunction "V_BKCP_36") (pintype "bidirectional"))
      (node (ref "U4") (pin "5") (pinfunction "OUT_5") (pintype "passive"))
    )
    (net (code "89") (name "ZED_DM") (class "Default")
      (node (ref "R28") (pin "1") (pinfunction "1_1") (pintype "passive"))
      (node (ref "U8") (pin "1") (pinfunction "USBDM_DN1_1") (pintype "bidirectional"))
    )
    (net (code "90") (name "ZED_DP") (class "Default")
      (node (ref "R27") (pin "1") (pinfunction "1_1") (pintype "passive"))
      (node (ref "U8") (pin "2") (pinfunction "USBDP_DN1_2") (pintype "bidirectional"))
    )
    (net (code "91") (name "ZED_EXTINT") (class "Default")
      (node (ref "R2") (pin "2") (pinfunction "2_2") (pintype "passive"))
      (node (ref "U1") (pin "5") (pinfunction "Y1_5") (pintype "bidirectional"))
    )
    (net (code "92") (name "ZED_FENCE_STAT") (class "Default")
      (node (ref "R40") (pin "2") (pinfunction "2_2") (pintype "passive"))
    )
    (net (code "93") (name "ZED_PPS_STAT") (class "Default")
      (node (ref "J4") (pin "2") (pinfunction "2_2") (pintype "passive"))
      (node (ref "R41") (pin "2") (pinfunction "2_2") (pintype "passive"))
      (node (ref "U1") (pin "14") (pinfunction "X1_14") (pintype "bidirectional"))
    )
    (net (code "94") (name "ZED_RTK_STAT") (class "Default")
      (node (ref "R39") (pin "2") (pinfunction "2_2") (pintype "passive"))
    )
    (net (code "95") (name "ZED_TX_READY") (class "Default")
      (node (ref "R35") (pin "2") (pinfunction "2_2") (pintype "passive"))
    )
    (net (code "96") (name "ZED_~{RESET}") (class "Default")
      (node (ref "R1") (pin "2") (pinfunction "2_2") (pintype "passive"))
    )
    (net (code "97") (name "ZED_~{SAFE}") (class "Default")
      (node (ref "R42") (pin "2") (pinfunction "2_2") (pintype "passive"))
    )
    (net (code "98") (name "unconnected-(J7-PAD1-PadNC1)") (class "Default")
      (node (ref "J7") (pin "NC1") (pinfunction "PAD1_NC1") (pintype "bidirectional"))
    )
    (net (code "99") (name "unconnected-(J7-PAD2-PadNC2)") (class "Default")
      (node (ref "J7") (pin "NC2") (pinfunction "PAD2_NC2") (pintype "bidirectional"))
    )
    (net (code "100") (name "unconnected-(J15-Pad5)") (class "Default")
      (node (ref "J15") (pin "5") (pinfunction "5_5") (pintype "bidirectional"))
    )
    (net (code "101") (name "unconnected-(U3-ANT_DETECT-Pad4)") (class "Default")
      (node (ref "U3") (pin "4") (pinfunction "ANT_DETECT_4") (pintype "bidirectional"))
    )
    (net (code "102") (name "unconnected-(U3-ANT_OFF-Pad5)") (class "Default")
      (node (ref "U3") (pin "5") (pinfunction "ANT_OFF_5") (pintype "bidirectional"))
    )
    (net (code "103") (name "unconnected-(U3-D_SEL-Pad47)") (class "Default")
      (node (ref "U3") (pin "47") (pinfunction "D_SEL_47") (pintype "bidirectional"))
    )
    (net (code "104") (name "unconnected-(U3-~{ANT_SHORT}-Pad6)") (class "Default")
      (node (ref "U3") (pin "6") (pinfunction "~{ANT_SHORT}_6") (pintype "bidirectional"))
    )
    (net (code "105") (name "unconnected-(U6-R232-Pad15)") (class "Default")
      (node (ref "U6") (pin "15") (pinfunction "R232_15") (pintype "bidirectional"))
    )
    (net (code "106") (name "unconnected-(U6-~{CTS}-Pad9)") (class "Default")
      (node (ref "U6") (pin "9") (pinfunction "~{CTS}_9") (pintype "bidirectional"))
    )
    (net (code "107") (name "unconnected-(U6-~{DCD}-Pad12)") (class "Default")
      (node (ref "U6") (pin "12") (pinfunction "~{DCD}_12") (pintype "bidirectional"))
    )
    (net (code "108") (name "unconnected-(U6-~{DSR}-Pad10)") (class "Default")
      (node (ref "U6") (pin "10") (pinfunction "~{DSR}_10") (pintype "bidirectional"))
    )
    (net (code "109") (name "unconnected-(U6-~{RI}-Pad11)") (class "Default")
      (node (ref "U6") (pin "11") (pinfunction "~{RI}_11") (pintype "bidirectional"))
    )
    (net (code "110") (name "unconnected-(U7-~{ALRT}-Pad5)") (class "Default")
      (node (ref "U7") (pin "5") (pinfunction "~{ALRT}_5") (pintype "bidirectional"))
    )
    (net (code "111") (name "unconnected-(U8-PRTPWR1-Pad12)") (class "Default")
      (node (ref "U8") (pin "12") (pinfunction "PRTPWR1_12") (pintype "bidirectional"))
    )
    (net (code "112") (name "unconnected-(U8-PRTPWR2-Pad16)") (class "Default")
      (node (ref "U8") (pin "16") (pinfunction "PRTPWR2_16") (pintype "bidirectional"))
    )
    (net (code "113") (name "unconnected-(U8-PRTPWR3-Pad18)") (class "Default")
      (node (ref "U8") (pin "18") (pinfunction "PRTPWR3_18") (pintype "bidirectional"))
    )
    (net (code "114") (name "unconnected-(U8-PRTPWR4-Pad20)") (class "Default")
      (node (ref "U8") (pin "20") (pinfunction "PRTPWR4_20") (pintype "bidirectional"))
    )
    (net (code "115") (name "unconnected-(U8-USBDM_DN3-Pad6)") (class "Default")
      (node (ref "U8") (pin "6") (pinfunction "USBDM_DN3_6") (pintype "bidirectional"))
    )
    (net (code "116") (name "unconnected-(U8-USBDM_DN4-Pad8)") (class "Default")
      (node (ref "U8") (pin "8") (pinfunction "USBDM_DN4_8") (pintype "bidirectional"))
    )
    (net (code "117") (name "unconnected-(U8-USBDP_DN3-Pad7)") (class "Default")
      (node (ref "U8") (pin "7") (pinfunction "USBDP_DN3_7") (pintype "bidirectional"))
    )
    (net (code "118") (name "unconnected-(U8-USBDP_DN4-Pad9)") (class "Default")
      (node (ref "U8") (pin "9") (pinfunction "USBDP_DN4_9") (pintype "bidirectional"))
    )
    (net (code "119") (name "unconnected-(U8-~{OCS1}-Pad13)") (class "Default")
      (node (ref "U8") (pin "13") (pinfunction "~{OCS1}_13") (pintype "bidirectional"))
    )
    (net (code "120") (name "unconnected-(U8-~{OCS2}-Pad17)") (class "Default")
      (node (ref "U8") (pin "17") (pinfunction "~{OCS2}_17") (pintype "bidirectional"))
    )
    (net (code "121") (name "unconnected-(U8-~{OCS3}-Pad19)") (class "Default")
      (node (ref "U8") (pin "19") (pinfunction "~{OCS3}_19") (pintype "bidirectional"))
    )
    (net (code "122") (name "unconnected-(U8-~{OCS4}-Pad21)") (class "Default")
      (node (ref "U8") (pin "21") (pinfunction "~{OCS4}_21") (pintype "bidirectional"))
    )
    (net (code "123") (name "unconnected-(U10-STAT2-Pad4)") (class "Default")
      (node (ref "U10") (pin "4") (pinfunction "STAT2_4") (pintype "bidirectional"))
    )
    (net (code "124") (name "unconnected-(U10-~{PG}-Pad7)") (class "Default")
      (node (ref "U10") (pin "7") (pinfunction "~{PG}_7") (pintype "bidirectional"))
    )
  )
)
